# FPS.net
KiCad netlist of a schematic drawn in Altium Designer
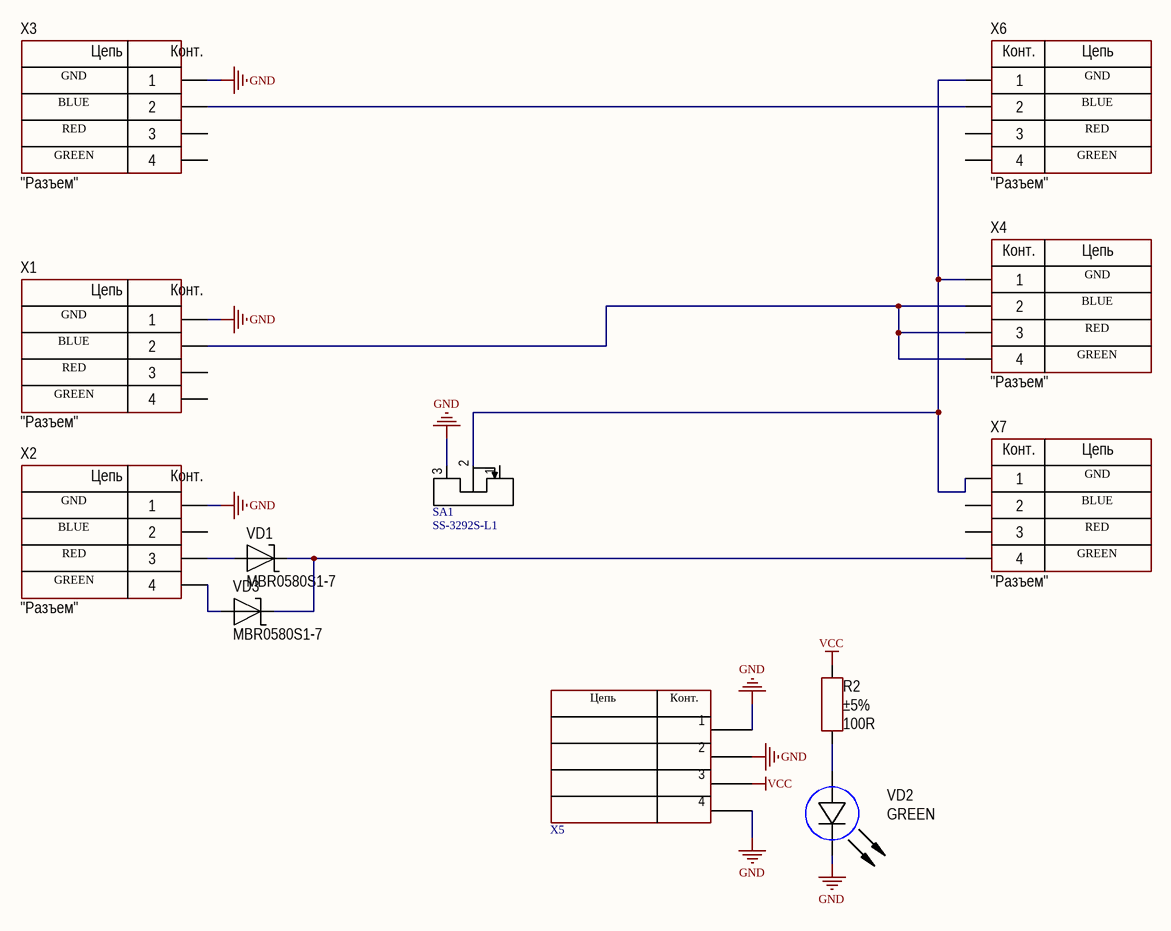
[diagram p0: FPS.SchDoc]

(export (version "E")
  (design (tool "Eeschema 10.0.6"))
  (components
    (comp (ref "R2")
      (value "100R")
      (footprint "RES: 0603")
      (fields
        (field (name "MANUFACTURER") "Yageo")
        (field (name "PARTNUMBER") "RC0603JR-07100RL")
        (field (name "VALUEMANUFACTURERPARTNUMBER") "Resistor film, 100R, ±5%, 0603, 0.1W, -55...+125°C")
        (field (name "TOLERANCE") "±5%")
      )
      (libsource (lib "Resistor") (part "Resistor_0603"))
    )
    (comp (ref "SA1")
      (value "SS-3292S-L1")
      (footprint "SS-3292S-L1")
      (libsource (lib "switch") (part "SS-3292S-L1"))
    )
    (comp (ref "VD1")
      (value "~")
      (footprint "DIODE: SOD523")
      (fields
        (field (name "MANUFACTURER") "Diodes Incorporated")
        (field (name "VALUEMANUFACTURERPARTNUMBER") "Schottky diode, 80V, 500mA, 1V, 15pF, SOD-123, -55...+150°C")
        (field (name "VOLTAGE") "80V")
        (field (name "PARTNUMBER") "MBR0580S1-7")
      )
      (libsource (lib "Diode") (part "Schottky_single"))
    )
    (comp (ref "VD2")
      (value "~")
      (footprint "LED: 1206R")
      (fields
        (field (name "VALUEMANUFACTURERPARTNUMBER") "LED, *, *, *, -55...+150°C")
        (field (name "COLOR") "GREEN")
      )
      (libsource (lib "Diode") (part "LED_single"))
    )
    (comp (ref "VD3")
      (value "~")
      (footprint "DIODE: SOD523")
      (fields
        (field (name "MANUFACTURER") "Diodes Incorporated")
        (field (name "VALUEMANUFACTURERPARTNUMBER") "Schottky diode, 80V, 500mA, 1V, 15pF, SOD-123, -55...+150°C")
        (field (name "VOLTAGE") "80V")
        (field (name "PARTNUMBER") "MBR0580S1-7")
      )
      (libsource (lib "Diode") (part "Schottky_single"))
    )
    (comp (ref "X1")
      (value "~")
      (footprint "CON: PBS-4 R")
      (fields
        (field (name "MANUFACTURER") "Connfly")
        (field (name "VALUEMANUFACTURERPARTNUMBER") "Connector, 4pin, 2.54mm, 500VAC, 3A")
        (field (name "PARTNUMBER") "PBS-4")
        (field (name "COMMENTTEXT") "\"Разъем\"")
      )
      (libsource (lib "Connector") (part "PBS-4"))
    )
    (comp (ref "X2")
      (value "~")
      (footprint "CON: PBS-4 R")
      (fields
        (field (name "MANUFACTURER") "Connfly")
        (field (name "VALUEMANUFACTURERPARTNUMBER") "Connector, 4pin, 2.54mm, 500VAC, 3A")
        (field (name "PARTNUMBER") "PBS-4")
        (field (name "COMMENTTEXT") "\"Разъем\"")
      )
      (libsource (lib "Connector") (part "PBS-4"))
    )
    (comp (ref "X3")
      (value "~")
      (footprint "CON: PBS-4 R")
      (fields
        (field (name "MANUFACTURER") "Connfly")
        (field (name "VALUEMANUFACTURERPARTNUMBER") "Connector, 4pin, 2.54mm, 500VAC, 3A")
        (field (name "PARTNUMBER") "PBS-4")
        (field (name "COMMENTTEXT") "\"Разъем\"")
      )
      (libsource (lib "Connector") (part "PBS-4"))
    )
    (comp (ref "X4")
      (value "~")
      (footprint "4PLS RIGHT ANGLE 2")
      (fields
        (field (name "MANUFACTURER") "Connfly")
        (field (name "VALUEMANUFACTURERPARTNUMBER") "Connector, 4pin, 2.54mm, 500VAC, 3A")
        (field (name "PARTNUMBER") "PLS-4")
        (field (name "COMMENTTEXT") "\"Разъем\"")
      )
      (libsource (lib "Connector") (part "PLS-4"))
    )
    (comp (ref "X5")
      (value "PBS-4 cut")
      (footprint "PBS-4 CUT")
      (libsource (lib "conect") (part "PBS-4 cut"))
    )
    (comp (ref "X6")
      (value "~")
      (footprint "4PLS RIGHT ANGLE 2")
      (fields
        (field (name "MANUFACTURER") "Connfly")
        (field (name "VALUEMANUFACTURERPARTNUMBER") "Connector, 4pin, 2.54mm, 500VAC, 3A")
        (field (name "PARTNUMBER") "PLS-4")
        (field (name "COMMENTTEXT") "\"Разъем\"")
      )
      (libsource (lib "Connector") (part "PLS-4"))
    )
    (comp (ref "X7")
      (value "~")
      (footprint "4PLS RIGHT ANGLE 2")
      (fields
        (field (name "MANUFACTURER") "Connfly")
        (field (name "VALUEMANUFACTURERPARTNUMBER") "Connector, 4pin, 2.54mm, 500VAC, 3A")
        (field (name "PARTNUMBER") "PLS-4")
        (field (name "COMMENTTEXT") "\"Разъем\"")
      )
      (libsource (lib "Connector") (part "PLS-4"))
    )
  )
  (nets
    (net (code "1") (name "GND") (class "Default")
      (node (ref "SA1") (pin "3") (pinfunction "3_3") (pintype "passive"))
      (node (ref "VD2") (pin "2") (pinfunction "C_2") (pintype "passive"))
      (node (ref "X1") (pin "1") (pinfunction "1_1") (pintype "passive"))
      (node (ref "X2") (pin "1") (pinfunction "1_1") (pintype "passive"))
      (node (ref "X3") (pin "1") (pinfunction "1_1") (pintype "passive"))
      (node (ref "X5") (pin "1") (pinfunction "1_1") (pintype "passive"))
      (node (ref "X5") (pin "2") (pinfunction "2_2") (pintype "passive"))
      (node (ref "X5") (pin "4") (pinfunction "4_4") (pintype "passive"))
    )
    (net (code "2") (name "Net-(SA1-Pad2)") (class "Default")
      (node (ref "SA1") (pin "2") (pinfunction "2_2") (pintype "passive"))
      (node (ref "X4") (pin "1") (pinfunction "1_1") (pintype "passive"))
      (node (ref "X6") (pin "1") (pinfunction "1_1") (pintype "passive"))
      (node (ref "X7") (pin "1") (pinfunction "1_1") (pintype "passive"))
    )
    (net (code "3") (name "Net-(VD1-Pad1)") (class "Default")
      (node (ref "VD1") (pin "1") (pinfunction "1_1") (pintype "passive"))
      (node (ref "X2") (pin "3") (pinfunction "3_3") (pintype "power_in"))
    )
    (net (code "4") (name "Net-(VD1-Pad2)") (class "Default")
      (node (ref "VD1") (pin "2") (pinfunction "2_2") (pintype "passive"))
      (node (ref "VD3") (pin "2") (pinfunction "2_2") (pintype "passive"))
      (node (ref "X7") (pin "4") (pinfunction "4_4") (pintype "power_in"))
    )
    (net (code "5") (name "Net-(VD2-A)") (class "Default")
      (node (ref "R2") (pin "1") (pinfunction "1_1") (pintype "passive"))
      (node (ref "VD2") (pin "1") (pinfunction "A_1") (pintype "passive"))
    )
    (net (code "6") (name "Net-(VD3-Pad1)") (class "Default")
      (node (ref "VD3") (pin "1") (pinfunction "1_1") (pintype "passive"))
      (node (ref "X2") (pin "4") (pinfunction "4_4") (pintype "power_in"))
    )
    (net (code "7") (name "Net-(X1-Pad2)") (class "Default")
      (node (ref "X1") (pin "2") (pinfunction "2_2") (pintype "passive"))
      (node (ref "X4") (pin "2") (pinfunction "2_2") (pintype "passive"))
      (node (ref "X4") (pin "3") (pinfunction "3_3") (pintype "power_in"))
      (node (ref "X4") (pin "4") (pinfunction "4_4") (pintype "power_in"))
    )
    (net (code "8") (name "Net-(X3-Pad2)") (class "Default")
      (node (ref "X3") (pin "2") (pinfunction "2_2") (pintype "passive"))
      (node (ref "X6") (pin "2") (pinfunction "2_2") (pintype "passive"))
    )
    (net (code "9") (name "VCC") (class "Default")
      (node (ref "R2") (pin "2") (pinfunction "2_2") (pintype "passive"))
      (node (ref "X5") (pin "3") (pinfunction "3_3") (pintype "passive"))
    )
    (net (code "10") (name "unconnected-(SA1-Pad1)") (class "Default")
      (node (ref "SA1") (pin "1") (pinfunction "1_1") (pintype "passive"))
    )
    (net (code "11") (name "unconnected-(X1-Pad3)") (class "Default")
      (node (ref "X1") (pin "3") (pinfunction "3_3") (pintype "power_in"))
    )
    (net (code "12") (name "unconnected-(X1-Pad4)") (class "Default")
      (node (ref "X1") (pin "4") (pinfunction "4_4") (pintype "power_in"))
    )
    (net (code "13") (name "unconnected-(X2-Pad2)") (class "Default")
      (node (ref "X2") (pin "2") (pinfunction "2_2") (pintype "passive"))
    )
    (net (code "14") (name "unconnected-(X3-Pad3)") (class "Default")
      (node (ref "X3") (pin "3") (pinfunction "3_3") (pintype "power_in"))
    )
    (net (code "15") (name "unconnected-(X3-Pad4)") (class "Default")
      (node (ref "X3") (pin "4") (pinfunction "4_4") (pintype "power_in"))
    )
    (net (code "16") (name "unconnected-(X6-Pad3)") (class "Default")
      (node (ref "X6") (pin "3") (pinfunction "3_3") (pintype "power_in"))
    )
    (net (code "17") (name "unconnected-(X6-Pad4)") (class "Default")
      (node (ref "X6") (pin "4") (pinfunction "4_4") (pintype "power_in"))
    )
    (net (code "18") (name "unconnected-(X7-Pad2)") (class "Default")
      (node (ref "X7") (pin "2") (pinfunction "2_2") (pintype "passive"))
    )
    (net (code "19") (name "unconnected-(X7-Pad3)") (class "Default")
      (node (ref "X7") (pin "3") (pinfunction "3_3") (pintype "power_in"))
    )
  )
)
